# mainboard_v6_0_2.net
KiCad netlist of a schematic drawn in EAGLE
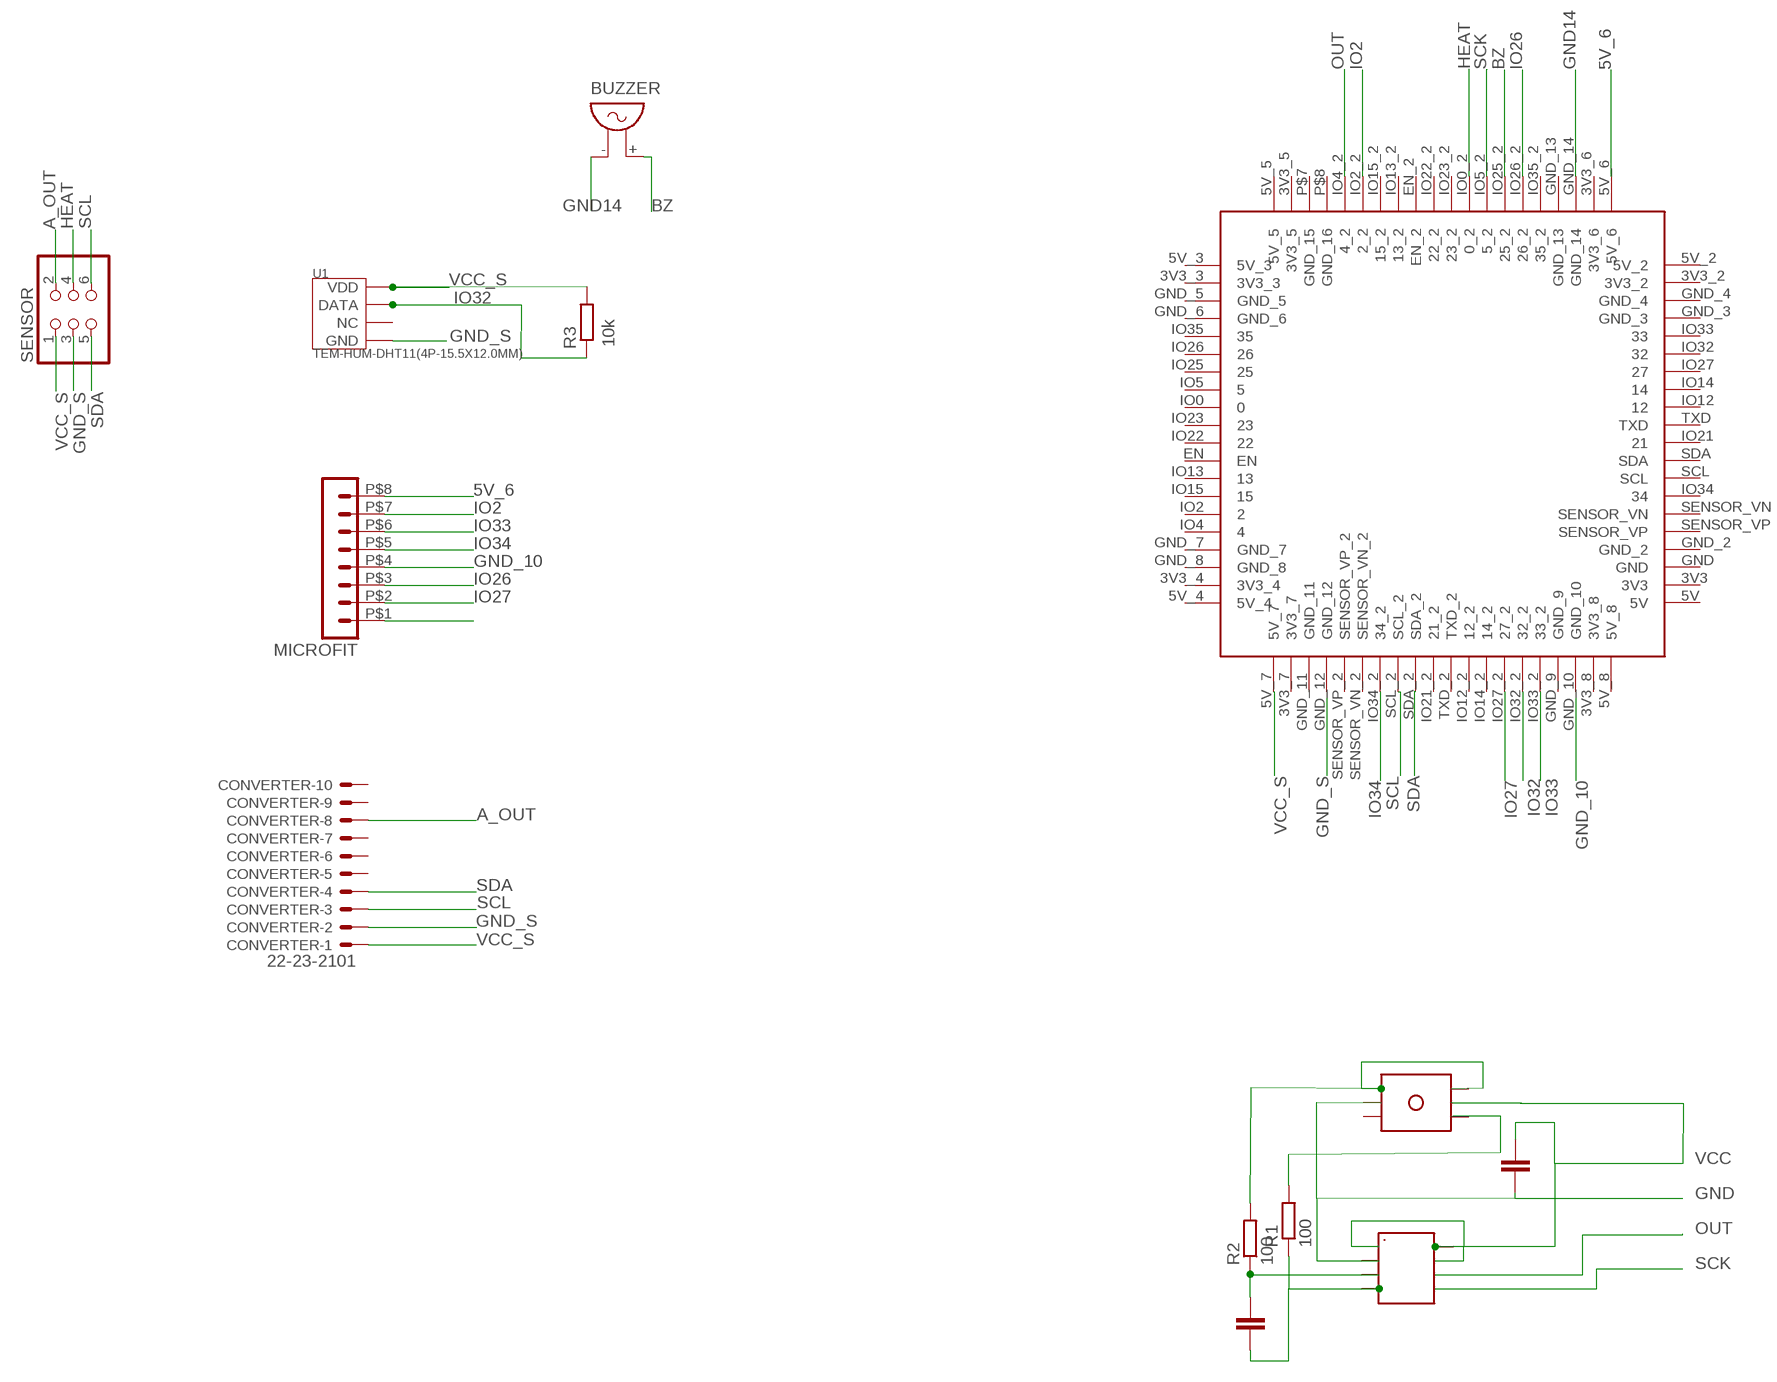
[diagram p0: schematic, sheet 1]

(export (version "E")
  (design (tool "Eeschema 10.0.6"))
  (components
    (comp (ref "BUZZER")
      (value "F/QMX")
      (footprint "eagle-import:F_QMX")
      (libsource (lib "eagle-import") (part "F/QMX"))
    )
    (comp (ref "C1")
      (value "100n")
      (footprint "eagle-import:C0805")
      (libsource (lib "eagle-import") (part "C-EUC0805"))
    )
    (comp (ref "C2")
      (value "100n")
      (footprint "eagle-import:C0805")
      (libsource (lib "eagle-import") (part "C-EUC0805"))
    )
    (comp (ref "CONVERTER")
      (value "22-23-2101")
      (footprint "eagle-import:22-23-2101")
      (fields (field (name "MF") "MOLEX"))
      (libsource (lib "eagle-import") (part "22-23-2101"))
    )
    (comp (ref "MICROFIT")
      (value "HEADER_POS8_43045-0800")
      (footprint "eagle-import:43045-0800")
      (libsource (lib "eagle-import") (part "HEADER_POS8_?43045-0800"))
    )
    (comp (ref "R1")
      (value "100")
      (footprint "eagle-import:R0805")
      (libsource (lib "eagle-import") (part "R-EU_R0805"))
    )
    (comp (ref "R2")
      (value "100")
      (footprint "eagle-import:R0805")
      (libsource (lib "eagle-import") (part "R-EU_R0805"))
    )
    (comp (ref "R3")
      (value "10k")
      (footprint "eagle-import:R0805")
      (libsource (lib "eagle-import") (part "R-EU_R0805"))
    )
    (comp (ref "SENSOR")
      (value "PINHD-2X3")
      (footprint "eagle-import:2X03")
      (libsource (lib "eagle-import") (part "PINHD-2X3"))
    )
    (comp (ref "U$1")
      (value "WT32_SC01WT32_D")
      (footprint "eagle-import:WT32_DUPLICATED")
      (libsource (lib "eagle-import") (part "WT32_SC01WT32_D"))
    )
    (comp (ref "U$2")
      (value "HX710B")
      (footprint "eagle-import:HX710B_SMD")
      (libsource (lib "eagle-import") (part "HX710B"))
    )
    (comp (ref "U$3")
      (value "PRESSUREPRESSURE_PTH")
      (footprint "eagle-import:PRESSURE_PTH")
      (libsource (lib "eagle-import") (part "PRESSUREPRESSURE_PTH"))
    )
    (comp (ref "U1")
      (value "TEM-HUM-DHT11(4P-15.5X12.0MM)")
      (footprint "eagle-import:SNR4-2.54-15.5X12.0X5.5MM")
      (fields (field (name "MF") "Panasonic Industrial Automation Sales") (field (name "MP") "DHT11"))
      (libsource (lib "eagle-import") (part "TEM-HUM-DHT11(4P-15.5X12.0MM)"))
    )
  )
  (nets
    (net (code "1") (name "/5V_6") (class "Default")
      (node (ref "MICROFIT") (pin "P$8") (pinfunction "8_P$8") (pintype "passive"))
      (node (ref "U$1") (pin "5V_6") (pinfunction "5V_6_5V_6") (pintype "bidirectional"))
    )
    (net (code "2") (name "/A_OUT") (class "Default")
      (node (ref "CONVERTER") (pin "8") (pinfunction "S_8") (pintype "passive"))
      (node (ref "SENSOR") (pin "2") (pinfunction "2_2") (pintype "passive"))
    )
    (net (code "3") (name "/BZ") (class "Default")
      (node (ref "BUZZER") (pin "+") (pinfunction "2_+") (pintype "passive"))
      (node (ref "U$1") (pin "IO25_2") (pinfunction "25_2_IO25_2") (pintype "bidirectional"))
    )
    (net (code "4") (name "/GND") (class "Default")
      (node (ref "C2") (pin "2") (pinfunction "2_2") (pintype "passive"))
      (node (ref "U$2") (pin "AGND") (pinfunction "AGND_AGND") (pintype "bidirectional"))
      (node (ref "U$3") (pin "2") (pinfunction "2_2") (pintype "bidirectional"))
    )
    (net (code "5") (name "/GND14") (class "Default")
      (node (ref "BUZZER") (pin "-") (pinfunction "1_-") (pintype "passive"))
      (node (ref "U$1") (pin "GND_14") (pinfunction "GND_14_GND_14") (pintype "bidirectional"))
    )
    (net (code "6") (name "/GND_10") (class "Default")
      (node (ref "MICROFIT") (pin "P$4") (pinfunction "4_P$4") (pintype "passive"))
      (node (ref "U$1") (pin "GND_10") (pinfunction "GND_10_GND_10") (pintype "bidirectional"))
    )
    (net (code "7") (name "/GND_S") (class "Default")
      (node (ref "CONVERTER") (pin "2") (pinfunction "S_2") (pintype "passive"))
      (node (ref "SENSOR") (pin "3") (pinfunction "3_3") (pintype "passive"))
      (node (ref "U$1") (pin "GND_12") (pinfunction "GND_12_GND_12") (pintype "bidirectional"))
      (node (ref "U1") (pin "4") (pinfunction "GND_4") (pintype "power_in"))
    )
    (net (code "8") (name "/HEAT") (class "Default")
      (node (ref "SENSOR") (pin "4") (pinfunction "4_4") (pintype "passive"))
      (node (ref "U$1") (pin "IO0_2") (pinfunction "0_2_IO0_2") (pintype "bidirectional"))
    )
    (net (code "9") (name "/IO2") (class "Default")
      (node (ref "MICROFIT") (pin "P$7") (pinfunction "7_P$7") (pintype "passive"))
      (node (ref "U$1") (pin "IO2_2") (pinfunction "2_2_IO2_2") (pintype "bidirectional"))
    )
    (net (code "10") (name "/IO26") (class "Default")
      (node (ref "MICROFIT") (pin "P$3") (pinfunction "3_P$3") (pintype "passive"))
      (node (ref "U$1") (pin "IO26_2") (pinfunction "26_2_IO26_2") (pintype "bidirectional"))
    )
    (net (code "11") (name "/IO27") (class "Default")
      (node (ref "MICROFIT") (pin "P$2") (pinfunction "2_P$2") (pintype "passive"))
      (node (ref "U$1") (pin "IO27_2") (pinfunction "27_2_IO27_2") (pintype "bidirectional"))
    )
    (net (code "12") (name "/IO32") (class "Default")
      (node (ref "R3") (pin "1") (pinfunction "1_1") (pintype "passive"))
      (node (ref "U$1") (pin "IO32_2") (pinfunction "32_2_IO32_2") (pintype "bidirectional"))
      (node (ref "U1") (pin "2") (pinfunction "DATA_2") (pintype "bidirectional"))
    )
    (net (code "13") (name "/IO33") (class "Default")
      (node (ref "MICROFIT") (pin "P$6") (pinfunction "6_P$6") (pintype "passive"))
      (node (ref "U$1") (pin "IO33_2") (pinfunction "33_2_IO33_2") (pintype "bidirectional"))
    )
    (net (code "14") (name "/IO34") (class "Default")
      (node (ref "MICROFIT") (pin "P$5") (pinfunction "5_P$5") (pintype "passive"))
      (node (ref "U$1") (pin "IO34_2") (pinfunction "34_2_IO34_2") (pintype "bidirectional"))
    )
    (net (code "15") (name "/N$5") (class "Default")
      (node (ref "R1") (pin "2") (pinfunction "2_2") (pintype "passive"))
      (node (ref "U$3") (pin "4") (pinfunction "4_4") (pintype "bidirectional"))
    )
    (net (code "16") (name "/N$7") (class "Default")
      (node (ref "R2") (pin "2") (pinfunction "2_2") (pintype "passive"))
      (node (ref "U$3") (pin "1") (pinfunction "1_1") (pintype "bidirectional"))
      (node (ref "U$3") (pin "6") (pinfunction "6_6") (pintype "bidirectional"))
    )
    (net (code "17") (name "/OUT") (class "Default")
      (node (ref "U$1") (pin "IO4_2") (pinfunction "4_2_IO4_2") (pintype "bidirectional"))
      (node (ref "U$2") (pin "DOUT") (pinfunction "DOUT_DOUT") (pintype "bidirectional"))
    )
    (net (code "18") (name "/SCK") (class "Default")
      (node (ref "U$1") (pin "IO5_2") (pinfunction "5_2_IO5_2") (pintype "bidirectional"))
      (node (ref "U$2") (pin "SCK") (pinfunction "SCK_SCK") (pintype "bidirectional"))
    )
    (net (code "19") (name "/SCL") (class "Default")
      (node (ref "CONVERTER") (pin "3") (pinfunction "S_3") (pintype "passive"))
      (node (ref "SENSOR") (pin "6") (pinfunction "6_6") (pintype "passive"))
      (node (ref "U$1") (pin "SCL_2") (pinfunction "SCL_2_SCL_2") (pintype "bidirectional"))
    )
    (net (code "20") (name "/SDA") (class "Default")
      (node (ref "CONVERTER") (pin "4") (pinfunction "S_4") (pintype "passive"))
      (node (ref "SENSOR") (pin "5") (pinfunction "5_5") (pintype "passive"))
      (node (ref "U$1") (pin "SDA_2") (pinfunction "SDA_2_SDA_2") (pintype "bidirectional"))
    )
    (net (code "21") (name "/VCC") (class "Default")
      (node (ref "C2") (pin "1") (pinfunction "1_1") (pintype "passive"))
      (node (ref "U$2") (pin "AVDD") (pinfunction "AVDD_AVDD") (pintype "bidirectional"))
      (node (ref "U$2") (pin "DVDD") (pinfunction "DVDD_DVDD") (pintype "bidirectional"))
      (node (ref "U$2") (pin "VREF") (pinfunction "VREF_VREF") (pintype "bidirectional"))
      (node (ref "U$3") (pin "5") (pinfunction "5_5") (pintype "bidirectional"))
    )
    (net (code "22") (name "/VCC_S") (class "Default")
      (node (ref "CONVERTER") (pin "1") (pinfunction "S_1") (pintype "passive"))
      (node (ref "R3") (pin "2") (pinfunction "2_2") (pintype "passive"))
      (node (ref "SENSOR") (pin "1") (pinfunction "1_1") (pintype "passive"))
      (node (ref "U$1") (pin "5V_7") (pinfunction "5V_7_5V_7") (pintype "bidirectional"))
      (node (ref "U1") (pin "1") (pinfunction "VDD_1") (pintype "power_in"))
    )
    (net (code "23") (name "Net-(C1-Pad1)") (class "Default")
      (node (ref "C1") (pin "1") (pinfunction "1_1") (pintype "passive"))
      (node (ref "R1") (pin "1") (pinfunction "1_1") (pintype "passive"))
      (node (ref "U$2") (pin "INP") (pinfunction "INP_INP") (pintype "bidirectional"))
    )
    (net (code "24") (name "Net-(C1-Pad2)") (class "Default")
      (node (ref "C1") (pin "2") (pinfunction "2_2") (pintype "passive"))
      (node (ref "R2") (pin "1") (pinfunction "1_1") (pintype "passive"))
      (node (ref "U$2") (pin "INN") (pinfunction "INN_INN") (pintype "bidirectional"))
    )
    (net (code "25") (name "unconnected-(CONVERTERB-S-Pad10)") (class "Default")
      (node (ref "CONVERTER") (pin "10") (pinfunction "S_10") (pintype "passive"))
    )
    (net (code "26") (name "unconnected-(CONVERTERF-S-Pad5)") (class "Default")
      (node (ref "CONVERTER") (pin "5") (pinfunction "S_5") (pintype "passive"))
    )
    (net (code "27") (name "unconnected-(CONVERTERG-S-Pad6)") (class "Default")
      (node (ref "CONVERTER") (pin "6") (pinfunction "S_6") (pintype "passive"))
    )
    (net (code "28") (name "unconnected-(CONVERTERH-S-Pad7)") (class "Default")
      (node (ref "CONVERTER") (pin "7") (pinfunction "S_7") (pintype "passive"))
    )
    (net (code "29") (name "unconnected-(CONVERTERJ-S-Pad9)") (class "Default")
      (node (ref "CONVERTER") (pin "9") (pinfunction "S_9") (pintype "passive"))
    )
    (net (code "30") (name "unconnected-(MICROFIT-1-PadP$1)") (class "Default")
      (node (ref "MICROFIT") (pin "P$1") (pinfunction "1_P$1") (pintype "passive"))
    )
    (net (code "31") (name "unconnected-(U$1-0-PadIO0)") (class "Default")
      (node (ref "U$1") (pin "IO0") (pinfunction "0_IO0") (pintype "bidirectional"))
    )
    (net (code "32") (name "unconnected-(U$1-2-PadIO2)") (class "Default")
      (node (ref "U$1") (pin "IO2") (pinfunction "2_IO2") (pintype "bidirectional"))
    )
    (net (code "33") (name "unconnected-(U$1-4-PadIO4)") (class "Default")
      (node (ref "U$1") (pin "IO4") (pinfunction "4_IO4") (pintype "bidirectional"))
    )
    (net (code "34") (name "unconnected-(U$1-5-PadIO5)") (class "Default")
      (node (ref "U$1") (pin "IO5") (pinfunction "5_IO5") (pintype "bidirectional"))
    )
    (net (code "35") (name "unconnected-(U$1-12-PadIO12)") (class "Default")
      (node (ref "U$1") (pin "IO12") (pinfunction "12_IO12") (pintype "bidirectional"))
    )
    (net (code "36") (name "unconnected-(U$1-12_2-PadIO12_2)") (class "Default")
      (node (ref "U$1") (pin "IO12_2") (pinfunction "12_2_IO12_2") (pintype "bidirectional"))
    )
    (net (code "37") (name "unconnected-(U$1-13-PadIO13)") (class "Default")
      (node (ref "U$1") (pin "IO13") (pinfunction "13_IO13") (pintype "bidirectional"))
    )
    (net (code "38") (name "unconnected-(U$1-13_2-PadIO13_2)") (class "Default")
      (node (ref "U$1") (pin "IO13_2") (pinfunction "13_2_IO13_2") (pintype "bidirectional"))
    )
    (net (code "39") (name "unconnected-(U$1-14-PadIO14)") (class "Default")
      (node (ref "U$1") (pin "IO14") (pinfunction "14_IO14") (pintype "bidirectional"))
    )
    (net (code "40") (name "unconnected-(U$1-14_2-PadIO14_2)") (class "Default")
      (node (ref "U$1") (pin "IO14_2") (pinfunction "14_2_IO14_2") (pintype "bidirectional"))
    )
    (net (code "41") (name "unconnected-(U$1-15-PadIO15)") (class "Default")
      (node (ref "U$1") (pin "IO15") (pinfunction "15_IO15") (pintype "bidirectional"))
    )
    (net (code "42") (name "unconnected-(U$1-15_2-PadIO15_2)") (class "Default")
      (node (ref "U$1") (pin "IO15_2") (pinfunction "15_2_IO15_2") (pintype "bidirectional"))
    )
    (net (code "43") (name "unconnected-(U$1-21-PadIO21)") (class "Default")
      (node (ref "U$1") (pin "IO21") (pinfunction "21_IO21") (pintype "bidirectional"))
    )
    (net (code "44") (name "unconnected-(U$1-21_2-PadIO21_2)") (class "Default")
      (node (ref "U$1") (pin "IO21_2") (pinfunction "21_2_IO21_2") (pintype "bidirectional"))
    )
    (net (code "45") (name "unconnected-(U$1-22-PadIO22)") (class "Default")
      (node (ref "U$1") (pin "IO22") (pinfunction "22_IO22") (pintype "bidirectional"))
    )
    (net (code "46") (name "unconnected-(U$1-22_2-PadIO22_2)") (class "Default")
      (node (ref "U$1") (pin "IO22_2") (pinfunction "22_2_IO22_2") (pintype "bidirectional"))
    )
    (net (code "47") (name "unconnected-(U$1-23-PadIO23)") (class "Default")
      (node (ref "U$1") (pin "IO23") (pinfunction "23_IO23") (pintype "bidirectional"))
    )
    (net (code "48") (name "unconnected-(U$1-23_2-PadIO23_2)") (class "Default")
      (node (ref "U$1") (pin "IO23_2") (pinfunction "23_2_IO23_2") (pintype "bidirectional"))
    )
    (net (code "49") (name "unconnected-(U$1-25-PadIO25)") (class "Default")
      (node (ref "U$1") (pin "IO25") (pinfunction "25_IO25") (pintype "bidirectional"))
    )
    (net (code "50") (name "unconnected-(U$1-26-PadIO26)") (class "Default")
      (node (ref "U$1") (pin "IO26") (pinfunction "26_IO26") (pintype "bidirectional"))
    )
    (net (code "51") (name "unconnected-(U$1-27-PadIO27)") (class "Default")
      (node (ref "U$1") (pin "IO27") (pinfunction "27_IO27") (pintype "bidirectional"))
    )
    (net (code "52") (name "unconnected-(U$1-32-PadIO32)") (class "Default")
      (node (ref "U$1") (pin "IO32") (pinfunction "32_IO32") (pintype "bidirectional"))
    )
    (net (code "53") (name "unconnected-(U$1-33-PadIO33)") (class "Default")
      (node (ref "U$1") (pin "IO33") (pinfunction "33_IO33") (pintype "bidirectional"))
    )
    (net (code "54") (name "unconnected-(U$1-34-PadIO34)") (class "Default")
      (node (ref "U$1") (pin "IO34") (pinfunction "34_IO34") (pintype "bidirectional"))
    )
    (net (code "55") (name "unconnected-(U$1-35-PadIO35)") (class "Default")
      (node (ref "U$1") (pin "IO35") (pinfunction "35_IO35") (pintype "bidirectional"))
    )
    (net (code "56") (name "unconnected-(U$1-35_2-PadIO35_2)") (class "Default")
      (node (ref "U$1") (pin "IO35_2") (pinfunction "35_2_IO35_2") (pintype "bidirectional"))
    )
    (net (code "57") (name "unconnected-(U$1-GND_15-PadP$7)") (class "Default")
      (node (ref "U$1") (pin "P$7") (pinfunction "GND_15_P$7") (pintype "bidirectional"))
    )
    (net (code "58") (name "unconnected-(U$1-GND_16-PadP$8)") (class "Default")
      (node (ref "U$1") (pin "P$8") (pinfunction "GND_16_P$8") (pintype "bidirectional"))
    )
    (net (code "59") (name "unconnected-(U$1-Pad3V3)") (class "Default")
      (node (ref "U$1") (pin "3V3") (pinfunction "3V3_3V3") (pintype "bidirectional"))
    )
    (net (code "60") (name "unconnected-(U$1-Pad3V3_2)") (class "Default")
      (node (ref "U$1") (pin "3V3_2") (pinfunction "3V3_2_3V3_2") (pintype "bidirectional"))
    )
    (net (code "61") (name "unconnected-(U$1-Pad3V3_3)") (class "Default")
      (node (ref "U$1") (pin "3V3_3") (pinfunction "3V3_3_3V3_3") (pintype "bidirectional"))
    )
    (net (code "62") (name "unconnected-(U$1-Pad3V3_4)") (class "Default")
      (node (ref "U$1") (pin "3V3_4") (pinfunction "3V3_4_3V3_4") (pintype "bidirectional"))
    )
    (net (code "63") (name "unconnected-(U$1-Pad3V3_5)") (class "Default")
      (node (ref "U$1") (pin "3V3_5") (pinfunction "3V3_5_3V3_5") (pintype "bidirectional"))
    )
    (net (code "64") (name "unconnected-(U$1-Pad3V3_6)") (class "Default")
      (node (ref "U$1") (pin "3V3_6") (pinfunction "3V3_6_3V3_6") (pintype "bidirectional"))
    )
    (net (code "65") (name "unconnected-(U$1-Pad3V3_7)") (class "Default")
      (node (ref "U$1") (pin "3V3_7") (pinfunction "3V3_7_3V3_7") (pintype "bidirectional"))
    )
    (net (code "66") (name "unconnected-(U$1-Pad3V3_8)") (class "Default")
      (node (ref "U$1") (pin "3V3_8") (pinfunction "3V3_8_3V3_8") (pintype "bidirectional"))
    )
    (net (code "67") (name "unconnected-(U$1-Pad5V)") (class "Default")
      (node (ref "U$1") (pin "5V") (pinfunction "5V_5V") (pintype "bidirectional"))
    )
    (net (code "68") (name "unconnected-(U$1-Pad5V_2)") (class "Default")
      (node (ref "U$1") (pin "5V_2") (pinfunction "5V_2_5V_2") (pintype "bidirectional"))
    )
    (net (code "69") (name "unconnected-(U$1-Pad5V_3)") (class "Default")
      (node (ref "U$1") (pin "5V_3") (pinfunction "5V_3_5V_3") (pintype "bidirectional"))
    )
    (net (code "70") (name "unconnected-(U$1-Pad5V_4)") (class "Default")
      (node (ref "U$1") (pin "5V_4") (pinfunction "5V_4_5V_4") (pintype "bidirectional"))
    )
    (net (code "71") (name "unconnected-(U$1-Pad5V_5)") (class "Default")
      (node (ref "U$1") (pin "5V_5") (pinfunction "5V_5_5V_5") (pintype "bidirectional"))
    )
    (net (code "72") (name "unconnected-(U$1-Pad5V_8)") (class "Default")
      (node (ref "U$1") (pin "5V_8") (pinfunction "5V_8_5V_8") (pintype "bidirectional"))
    )
    (net (code "73") (name "unconnected-(U$1-PadEN)") (class "Default")
      (node (ref "U$1") (pin "EN") (pinfunction "EN_EN") (pintype "bidirectional"))
    )
    (net (code "74") (name "unconnected-(U$1-PadEN_2)") (class "Default")
      (node (ref "U$1") (pin "EN_2") (pinfunction "EN_2_EN_2") (pintype "bidirectional"))
    )
    (net (code "75") (name "unconnected-(U$1-PadGND)") (class "Default")
      (node (ref "U$1") (pin "GND") (pinfunction "GND_GND") (pintype "bidirectional"))
    )
    (net (code "76") (name "unconnected-(U$1-PadGND_2)") (class "Default")
      (node (ref "U$1") (pin "GND_2") (pinfunction "GND_2_GND_2") (pintype "bidirectional"))
    )
    (net (code "77") (name "unconnected-(U$1-PadGND_3)") (class "Default")
      (node (ref "U$1") (pin "GND_3") (pinfunction "GND_3_GND_3") (pintype "bidirectional"))
    )
    (net (code "78") (name "unconnected-(U$1-PadGND_4)") (class "Default")
      (node (ref "U$1") (pin "GND_4") (pinfunction "GND_4_GND_4") (pintype "bidirectional"))
    )
    (net (code "79") (name "unconnected-(U$1-PadGND_5)") (class "Default")
      (node (ref "U$1") (pin "GND_5") (pinfunction "GND_5_GND_5") (pintype "bidirectional"))
    )
    (net (code "80") (name "unconnected-(U$1-PadGND_6)") (class "Default")
      (node (ref "U$1") (pin "GND_6") (pinfunction "GND_6_GND_6") (pintype "bidirectional"))
    )
    (net (code "81") (name "unconnected-(U$1-PadGND_7)") (class "Default")
      (node (ref "U$1") (pin "GND_7") (pinfunction "GND_7_GND_7") (pintype "bidirectional"))
    )
    (net (code "82") (name "unconnected-(U$1-PadGND_8)") (class "Default")
      (node (ref "U$1") (pin "GND_8") (pinfunction "GND_8_GND_8") (pintype "bidirectional"))
    )
    (net (code "83") (name "unconnected-(U$1-PadGND_9)") (class "Default")
      (node (ref "U$1") (pin "GND_9") (pinfunction "GND_9_GND_9") (pintype "bidirectional"))
    )
    (net (code "84") (name "unconnected-(U$1-PadGND_11)") (class "Default")
      (node (ref "U$1") (pin "GND_11") (pinfunction "GND_11_GND_11") (pintype "bidirectional"))
    )
    (net (code "85") (name "unconnected-(U$1-PadGND_13)") (class "Default")
      (node (ref "U$1") (pin "GND_13") (pinfunction "GND_13_GND_13") (pintype "bidirectional"))
    )
    (net (code "86") (name "unconnected-(U$1-PadSCL)") (class "Default")
      (node (ref "U$1") (pin "SCL") (pinfunction "SCL_SCL") (pintype "bidirectional"))
    )
    (net (code "87") (name "unconnected-(U$1-PadSDA)") (class "Default")
      (node (ref "U$1") (pin "SDA") (pinfunction "SDA_SDA") (pintype "bidirectional"))
    )
    (net (code "88") (name "unconnected-(U$1-PadSENSOR_VN)") (class "Default")
      (node (ref "U$1") (pin "SENSOR_VN") (pinfunction "SENSOR_VN_SENSOR_VN") (pintype "bidirectional"))
    )
    (net (code "89") (name "unconnected-(U$1-PadSENSOR_VN_2)") (class "Default")
      (node (ref "U$1") (pin "SENSOR_VN_2") (pinfunction "SENSOR_VN_2_SENSOR_VN_2") (pintype "bidirectional"))
    )
    (net (code "90") (name "unconnected-(U$1-PadSENSOR_VP)") (class "Default")
      (node (ref "U$1") (pin "SENSOR_VP") (pinfunction "SENSOR_VP_SENSOR_VP") (pintype "bidirectional"))
    )
    (net (code "91") (name "unconnected-(U$1-PadSENSOR_VP_2)") (class "Default")
      (node (ref "U$1") (pin "SENSOR_VP_2") (pinfunction "SENSOR_VP_2_SENSOR_VP_2") (pintype "bidirectional"))
    )
    (net (code "92") (name "unconnected-(U$1-PadTXD)") (class "Default")
      (node (ref "U$1") (pin "TXD") (pinfunction "TXD_TXD") (pintype "bidirectional"))
    )
    (net (code "93") (name "unconnected-(U$1-PadTXD_2)") (class "Default")
      (node (ref "U$1") (pin "TXD_2") (pinfunction "TXD_2_TXD_2") (pintype "bidirectional"))
    )
    (net (code "94") (name "unconnected-(U$3-Pad3)") (class "Default")
      (node (ref "U$3") (pin "3") (pinfunction "3_3") (pintype "bidirectional"))
    )
    (net (code "95") (name "unconnected-(U1-NC-Pad3)") (class "Default")
      (node (ref "U1") (pin "3") (pinfunction "NC_3") (pintype "no_connect"))
    )
  )
)
